# Main-board-4.net
KiCad netlist of a schematic drawn in EAGLE
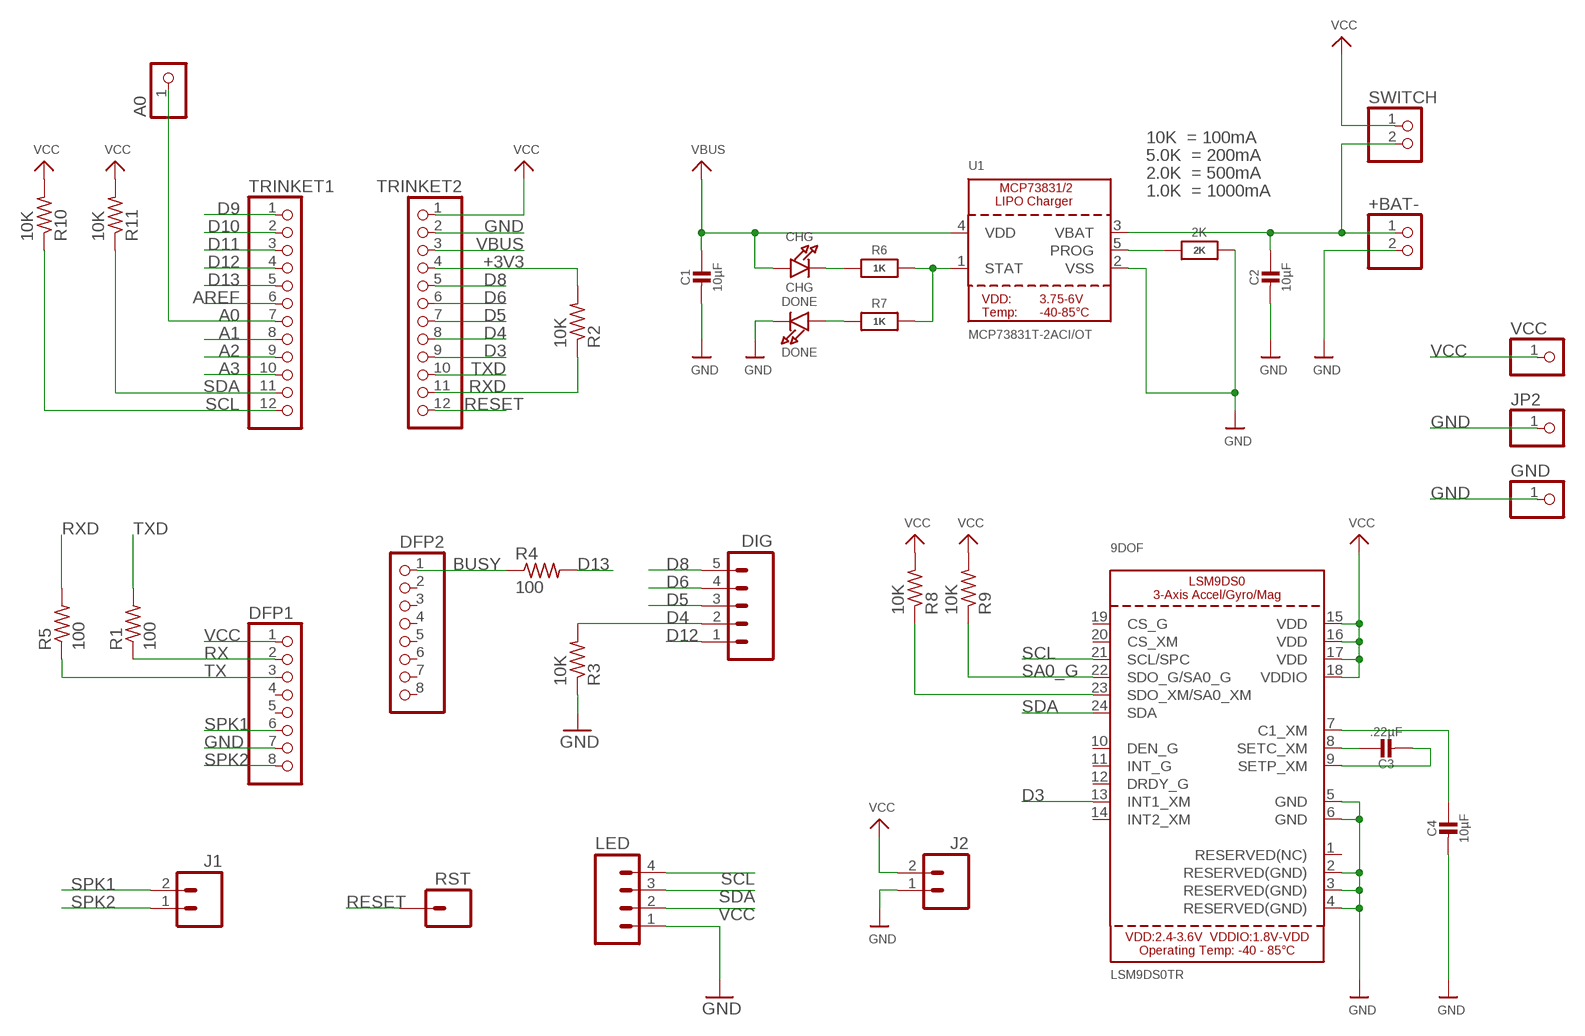
[diagram p0: schematic, sheet 1]

(export (version "E")
  (design (tool "Eeschema 10.0.6"))
  (components
    (comp (ref "+BAT-")
      (value "HEADER-1X2ROUND")
      (footprint "eagle-import:1X02_ROUND")
      (libsource (lib "eagle-import") (part "HEADER-1X2ROUND"))
    )
    (comp (ref "2K")
      (value "2K")
      (footprint "eagle-import:_0805MP")
      (libsource (lib "eagle-import") (part "RESISTOR_0805MP"))
    )
    (comp (ref "9DOF")
      (value "LSM9DS0TR")
      (footprint "eagle-import:LGA24_4X4MM")
      (libsource (lib "eagle-import") (part "LSM9DS0"))
    )
    (comp (ref "A0")
      (value "PINHD-1X1CB")
      (footprint "eagle-import:1X01-CLEANBIG")
      (libsource (lib "eagle-import") (part "PINHD-1X1CB"))
    )
    (comp (ref "C1")
      (value "10µF")
      (footprint "eagle-import:0805-NO")
      (libsource (lib "eagle-import") (part "CAP_CERAMIC0805-NOOUTLINE"))
    )
    (comp (ref "C2")
      (value "10µF")
      (footprint "eagle-import:0805-NO")
      (libsource (lib "eagle-import") (part "CAP_CERAMIC0805-NOOUTLINE"))
    )
    (comp (ref "C3")
      (value ".22µF")
      (footprint "eagle-import:0805-NO")
      (libsource (lib "eagle-import") (part "CAP_CERAMIC0805-NOOUTLINE"))
    )
    (comp (ref "C4")
      (value "10µF")
      (footprint "eagle-import:0805-NO")
      (libsource (lib "eagle-import") (part "CAP_CERAMIC0805-NOOUTLINE"))
    )
    (comp (ref "CHG")
      (value "CHG")
      (footprint "eagle-import:CHIPLED_0805_NOOUTLINE")
      (libsource (lib "eagle-import") (part "LED0805_NOOUTLINE"))
    )
    (comp (ref "DFP1")
      (value "PINHD-1X8CLEANBIG")
      (footprint "eagle-import:1X08-CLEANBIG")
      (libsource (lib "eagle-import") (part "PINHD-1X8CLEANBIG"))
    )
    (comp (ref "DFP2")
      (value "PINHD-1X8CLEANBIG")
      (footprint "eagle-import:1X08-CLEANBIG")
      (libsource (lib "eagle-import") (part "PINHD-1X8CLEANBIG"))
    )
    (comp (ref "DIG")
      (value "M05NO_SILK")
      (footprint "eagle-import:1X05_NO_SILK")
      (libsource (lib "eagle-import") (part "M05NO_SILK"))
    )
    (comp (ref "DONE")
      (value "DONE")
      (footprint "eagle-import:CHIPLED_0805_NOOUTLINE")
      (libsource (lib "eagle-import") (part "LED0805_NOOUTLINE"))
    )
    (comp (ref "GND")
      (value "PINHD-1X1CB")
      (footprint "eagle-import:1X01-CLEANBIG")
      (libsource (lib "eagle-import") (part "PINHD-1X1CB"))
    )
    (comp (ref "J1")
      (value "M021X02_NO_SILK")
      (footprint "eagle-import:1X02_NO_SILK")
      (libsource (lib "eagle-import") (part "M021X02_NO_SILK"))
    )
    (comp (ref "J2")
      (value "M021X02_NO_SILK")
      (footprint "eagle-import:1X02_NO_SILK")
      (libsource (lib "eagle-import") (part "M021X02_NO_SILK"))
    )
    (comp (ref "JP2")
      (value "PINHD-1X1CB")
      (footprint "eagle-import:1X01-CLEANBIG")
      (libsource (lib "eagle-import") (part "PINHD-1X1CB"))
    )
    (comp (ref "LED")
      (value "M04NO_SILK_ALL_ROUND")
      (footprint "eagle-import:1X04_NO_SILK_ALL_ROUND")
      (libsource (lib "eagle-import") (part "M04NO_SILK_ALL_ROUND"))
    )
    (comp (ref "R1")
      (value "100")
      (footprint "eagle-import:R0805")
      (libsource (lib "eagle-import") (part "R-US_R0805"))
    )
    (comp (ref "R2")
      (value "10K")
      (footprint "eagle-import:R0805")
      (libsource (lib "eagle-import") (part "R-US_R0805"))
    )
    (comp (ref "R3")
      (value "10K")
      (footprint "eagle-import:R0805")
      (libsource (lib "eagle-import") (part "R-US_R0805"))
    )
    (comp (ref "R4")
      (value "100")
      (footprint "eagle-import:R0805")
      (libsource (lib "eagle-import") (part "R-US_R0805"))
    )
    (comp (ref "R5")
      (value "100")
      (footprint "eagle-import:R0805")
      (libsource (lib "eagle-import") (part "R-US_R0805"))
    )
    (comp (ref "R6")
      (value "1K")
      (footprint "eagle-import:0805-NO")
      (libsource (lib "eagle-import") (part "RESISTOR0805_NOOUTLINE"))
    )
    (comp (ref "R7")
      (value "1K")
      (footprint "eagle-import:0805-NO")
      (libsource (lib "eagle-import") (part "RESISTOR0805_NOOUTLINE"))
    )
    (comp (ref "R8")
      (value "10K")
      (footprint "eagle-import:R0805")
      (libsource (lib "eagle-import") (part "R-US_R0805"))
    )
    (comp (ref "R9")
      (value "10K")
      (footprint "eagle-import:R0805")
      (libsource (lib "eagle-import") (part "R-US_R0805"))
    )
    (comp (ref "R10")
      (value "10K")
      (footprint "eagle-import:R0805")
      (libsource (lib "eagle-import") (part "R-US_R0805"))
    )
    (comp (ref "R11")
      (value "10K")
      (footprint "eagle-import:R0805")
      (libsource (lib "eagle-import") (part "R-US_R0805"))
    )
    (comp (ref "RST")
      (value "M01PTH_NO_SILK_YES_STOP")
      (footprint "eagle-import:1X01_NO_SILK")
      (libsource (lib "eagle-import") (part "M01PTH_NO_SILK_YES_STOP"))
    )
    (comp (ref "SWITCH")
      (value "HEADER-1X2ROUND")
      (footprint "eagle-import:1X02_ROUND")
      (libsource (lib "eagle-import") (part "HEADER-1X2ROUND"))
    )
    (comp (ref "TRINKET1")
      (value "PINHD-1X12-CB")
      (footprint "eagle-import:1X12-CB")
      (libsource (lib "eagle-import") (part "PINHD-1X12-CB"))
    )
    (comp (ref "TRINKET2")
      (value "PINHD-1X12-CB")
      (footprint "eagle-import:1X12-CB")
      (libsource (lib "eagle-import") (part "PINHD-1X12-CB"))
    )
    (comp (ref "U1")
      (value "MCP73831T-2ACI/OT")
      (footprint "eagle-import:SOT23-5")
      (libsource (lib "eagle-import") (part "MCP73831/2"))
    )
    (comp (ref "VCC")
      (value "PINHD-1X1CB")
      (footprint "eagle-import:1X01-CLEANBIG")
      (libsource (lib "eagle-import") (part "PINHD-1X1CB"))
    )
  )
  (nets
    (net (code "1") (name "/+3V3") (class "Default")
      (node (ref "R2") (pin "2") (pinfunction "2_2") (pintype "passive"))
      (node (ref "TRINKET2") (pin "4") (pinfunction "4_4") (pintype "passive"))
    )
    (net (code "2") (name "/A0") (class "Default")
      (node (ref "A0") (pin "1") (pinfunction "1_1") (pintype "passive"))
      (node (ref "TRINKET1") (pin "7") (pinfunction "7_7") (pintype "passive"))
    )
    (net (code "3") (name "/A1") (class "Default")
      (node (ref "TRINKET1") (pin "8") (pinfunction "8_8") (pintype "passive"))
    )
    (net (code "4") (name "/A2") (class "Default")
      (node (ref "TRINKET1") (pin "9") (pinfunction "9_9") (pintype "passive"))
    )
    (net (code "5") (name "/A3") (class "Default")
      (node (ref "TRINKET1") (pin "10") (pinfunction "10_10") (pintype "passive"))
    )
    (net (code "6") (name "/AREF") (class "Default")
      (node (ref "TRINKET1") (pin "6") (pinfunction "6_6") (pintype "passive"))
    )
    (net (code "7") (name "/BUSY") (class "Default")
      (node (ref "DFP2") (pin "1") (pinfunction "1_1") (pintype "passive"))
      (node (ref "R4") (pin "1") (pinfunction "1_1") (pintype "passive"))
    )
    (net (code "8") (name "/D3") (class "Default")
      (node (ref "9DOF") (pin "13") (pinfunction "INT1_XM_13") (pintype "bidirectional"))
      (node (ref "TRINKET2") (pin "9") (pinfunction "9_9") (pintype "passive"))
    )
    (net (code "9") (name "/D4") (class "Default")
      (node (ref "DIG") (pin "2") (pinfunction "2_2") (pintype "passive"))
      (node (ref "R3") (pin "2") (pinfunction "2_2") (pintype "passive"))
      (node (ref "TRINKET2") (pin "8") (pinfunction "8_8") (pintype "passive"))
    )
    (net (code "10") (name "/D5") (class "Default")
      (node (ref "DIG") (pin "3") (pinfunction "3_3") (pintype "passive"))
      (node (ref "TRINKET2") (pin "7") (pinfunction "7_7") (pintype "passive"))
    )
    (net (code "11") (name "/D6") (class "Default")
      (node (ref "DIG") (pin "4") (pinfunction "4_4") (pintype "passive"))
      (node (ref "TRINKET2") (pin "6") (pinfunction "6_6") (pintype "passive"))
    )
    (net (code "12") (name "/D8") (class "Default")
      (node (ref "DIG") (pin "5") (pinfunction "5_5") (pintype "passive"))
      (node (ref "TRINKET2") (pin "5") (pinfunction "5_5") (pintype "passive"))
    )
    (net (code "13") (name "/D9") (class "Default")
      (node (ref "TRINKET1") (pin "1") (pinfunction "1_1") (pintype "passive"))
    )
    (net (code "14") (name "/D10") (class "Default")
      (node (ref "TRINKET1") (pin "2") (pinfunction "2_2") (pintype "passive"))
    )
    (net (code "15") (name "/D11") (class "Default")
      (node (ref "TRINKET1") (pin "3") (pinfunction "3_3") (pintype "passive"))
    )
    (net (code "16") (name "/D12") (class "Default")
      (node (ref "DIG") (pin "1") (pinfunction "1_1") (pintype "passive"))
      (node (ref "TRINKET1") (pin "4") (pinfunction "4_4") (pintype "passive"))
    )
    (net (code "17") (name "/D13") (class "Default")
      (node (ref "R4") (pin "2") (pinfunction "2_2") (pintype "passive"))
      (node (ref "TRINKET1") (pin "5") (pinfunction "5_5") (pintype "passive"))
    )
    (net (code "18") (name "/RESET") (class "Default")
      (node (ref "RST") (pin "1") (pinfunction "1_1") (pintype "passive"))
      (node (ref "TRINKET2") (pin "12") (pinfunction "12_12") (pintype "passive"))
    )
    (net (code "19") (name "/RX") (class "Default")
      (node (ref "DFP1") (pin "2") (pinfunction "2_2") (pintype "passive"))
      (node (ref "R1") (pin "1") (pinfunction "1_1") (pintype "passive"))
    )
    (net (code "20") (name "/RXD") (class "Default")
      (node (ref "R2") (pin "1") (pinfunction "1_1") (pintype "passive"))
      (node (ref "R5") (pin "2") (pinfunction "2_2") (pintype "passive"))
      (node (ref "TRINKET2") (pin "11") (pinfunction "11_11") (pintype "passive"))
    )
    (net (code "21") (name "/SA0_G") (class "Default")
      (node (ref "9DOF") (pin "22") (pinfunction "SDO_G/SA0_G_22") (pintype "bidirectional"))
      (node (ref "R9") (pin "1") (pinfunction "1_1") (pintype "passive"))
    )
    (net (code "22") (name "/SCL") (class "Default")
      (node (ref "9DOF") (pin "21") (pinfunction "SCL/SPC_21") (pintype "bidirectional"))
      (node (ref "LED") (pin "4") (pinfunction "4_4") (pintype "passive"))
      (node (ref "R10") (pin "1") (pinfunction "1_1") (pintype "passive"))
      (node (ref "TRINKET1") (pin "12") (pinfunction "12_12") (pintype "passive"))
    )
    (net (code "23") (name "/SDA") (class "Default")
      (node (ref "9DOF") (pin "24") (pinfunction "SDA_24") (pintype "bidirectional"))
      (node (ref "LED") (pin "3") (pinfunction "3_3") (pintype "passive"))
      (node (ref "R11") (pin "1") (pinfunction "1_1") (pintype "passive"))
      (node (ref "TRINKET1") (pin "11") (pinfunction "11_11") (pintype "passive"))
    )
    (net (code "24") (name "/SPK1") (class "Default")
      (node (ref "DFP1") (pin "6") (pinfunction "6_6") (pintype "passive"))
      (node (ref "J1") (pin "2") (pinfunction "2_2") (pintype "passive"))
    )
    (net (code "25") (name "/SPK2") (class "Default")
      (node (ref "DFP1") (pin "8") (pinfunction "8_8") (pintype "passive"))
      (node (ref "J1") (pin "1") (pinfunction "1_1") (pintype "passive"))
    )
    (net (code "26") (name "/TX") (class "Default")
      (node (ref "DFP1") (pin "3") (pinfunction "3_3") (pintype "passive"))
      (node (ref "R5") (pin "1") (pinfunction "1_1") (pintype "passive"))
    )
    (net (code "27") (name "/TXD") (class "Default")
      (node (ref "R1") (pin "2") (pinfunction "2_2") (pintype "passive"))
      (node (ref "TRINKET2") (pin "10") (pinfunction "10_10") (pintype "passive"))
    )
    (net (code "28") (name "GND") (class "Default")
      (node (ref "+BAT-") (pin "2") (pinfunction "2_2") (pintype "passive"))
      (node (ref "2K") (pin "2") (pinfunction "2_2") (pintype "passive"))
      (node (ref "9DOF") (pin "2") (pinfunction "RESERVED(GND)_2") (pintype "power_in"))
      (node (ref "9DOF") (pin "3") (pinfunction "RESERVED(GND)_3") (pintype "power_in"))
      (node (ref "9DOF") (pin "4") (pinfunction "RESERVED(GND)_4") (pintype "power_in"))
      (node (ref "9DOF") (pin "5") (pinfunction "GND_5") (pintype "power_in"))
      (node (ref "9DOF") (pin "6") (pinfunction "GND_6") (pintype "power_in"))
      (node (ref "C1") (pin "2") (pinfunction "2_2") (pintype "passive"))
      (node (ref "C2") (pin "2") (pinfunction "2_2") (pintype "passive"))
      (node (ref "C4") (pin "2") (pinfunction "2_2") (pintype "passive"))
      (node (ref "DFP1") (pin "7") (pinfunction "7_7") (pintype "passive"))
      (node (ref "DONE") (pin "C") (pinfunction "C_C") (pintype "passive"))
      (node (ref "GND") (pin "1") (pinfunction "1_1") (pintype "passive"))
      (node (ref "J2") (pin "1") (pinfunction "1_1") (pintype "passive"))
      (node (ref "JP2") (pin "1") (pinfunction "1_1") (pintype "passive"))
      (node (ref "LED") (pin "1") (pinfunction "1_1") (pintype "passive"))
      (node (ref "R3") (pin "1") (pinfunction "1_1") (pintype "passive"))
      (node (ref "TRINKET2") (pin "2") (pinfunction "2_2") (pintype "passive"))
      (node (ref "U1") (pin "2") (pinfunction "VSS_2") (pintype "power_in"))
    )
    (net (code "29") (name "Net-(9DOF-C1_XM)") (class "Default")
      (node (ref "9DOF") (pin "7") (pinfunction "C1_XM_7") (pintype "bidirectional"))
      (node (ref "C4") (pin "1") (pinfunction "1_1") (pintype "passive"))
    )
    (net (code "30") (name "Net-(9DOF-SDO_XM{slash}SA0_XM)") (class "Default")
      (node (ref "9DOF") (pin "23") (pinfunction "SDO_XM/SA0_XM_23") (pintype "bidirectional"))
      (node (ref "R8") (pin "1") (pinfunction "1_1") (pintype "passive"))
    )
    (net (code "31") (name "Net-(9DOF-SETC_XM)") (class "Default")
      (node (ref "9DOF") (pin "8") (pinfunction "SETC_XM_8") (pintype "bidirectional"))
      (node (ref "C3") (pin "1") (pinfunction "1_1") (pintype "passive"))
    )
    (net (code "32") (name "Net-(9DOF-SETP_XM)") (class "Default")
      (node (ref "9DOF") (pin "9") (pinfunction "SETP_XM_9") (pintype "bidirectional"))
      (node (ref "C3") (pin "2") (pinfunction "2_2") (pintype "passive"))
    )
    (net (code "33") (name "Net-(CHG-PadC)") (class "Default")
      (node (ref "CHG") (pin "C") (pinfunction "C_C") (pintype "passive"))
      (node (ref "R6") (pin "1") (pinfunction "1_1") (pintype "passive"))
    )
    (net (code "34") (name "Net-(DONE-PadA)") (class "Default")
      (node (ref "DONE") (pin "A") (pinfunction "A_A") (pintype "passive"))
      (node (ref "R7") (pin "1") (pinfunction "1_1") (pintype "passive"))
    )
    (net (code "35") (name "Net-(U1-PROG)") (class "Default")
      (node (ref "2K") (pin "1") (pinfunction "1_1") (pintype "passive"))
      (node (ref "U1") (pin "5") (pinfunction "PROG_5") (pintype "input"))
    )
    (net (code "36") (name "Net-(U1-STAT)") (class "Default")
      (node (ref "R6") (pin "2") (pinfunction "2_2") (pintype "passive"))
      (node (ref "R7") (pin "2") (pinfunction "2_2") (pintype "passive"))
      (node (ref "U1") (pin "1") (pinfunction "STAT_1") (pintype "output"))
    )
    (net (code "37") (name "Net-(U1-VBAT)") (class "Default")
      (node (ref "+BAT-") (pin "1") (pinfunction "1_1") (pintype "passive"))
      (node (ref "C2") (pin "1") (pinfunction "1_1") (pintype "passive"))
      (node (ref "SWITCH") (pin "2") (pinfunction "2_2") (pintype "passive"))
      (node (ref "U1") (pin "3") (pinfunction "VBAT_3") (pintype "power_in"))
    )
    (net (code "38") (name "VBUS") (class "Default")
      (node (ref "C1") (pin "1") (pinfunction "1_1") (pintype "passive"))
      (node (ref "CHG") (pin "A") (pinfunction "A_A") (pintype "passive"))
      (node (ref "TRINKET2") (pin "3") (pinfunction "3_3") (pintype "passive"))
      (node (ref "U1") (pin "4") (pinfunction "VDD_4") (pintype "power_in"))
    )
    (net (code "39") (name "VCC") (class "Default")
      (node (ref "9DOF") (pin "15") (pinfunction "VDD_15") (pintype "power_in"))
      (node (ref "9DOF") (pin "16") (pinfunction "VDD_16") (pintype "power_in"))
      (node (ref "9DOF") (pin "17") (pinfunction "VDD_17") (pintype "power_in"))
      (node (ref "9DOF") (pin "18") (pinfunction "VDDIO_18") (pintype "power_in"))
      (node (ref "DFP1") (pin "1") (pinfunction "1_1") (pintype "passive"))
      (node (ref "J2") (pin "2") (pinfunction "2_2") (pintype "passive"))
      (node (ref "LED") (pin "2") (pinfunction "2_2") (pintype "passive"))
      (node (ref "R10") (pin "2") (pinfunction "2_2") (pintype "passive"))
      (node (ref "R11") (pin "2") (pinfunction "2_2") (pintype "passive"))
      (node (ref "R8") (pin "2") (pinfunction "2_2") (pintype "passive"))
      (node (ref "R9") (pin "2") (pinfunction "2_2") (pintype "passive"))
      (node (ref "SWITCH") (pin "1") (pinfunction "1_1") (pintype "passive"))
      (node (ref "TRINKET2") (pin "1") (pinfunction "1_1") (pintype "passive"))
      (node (ref "VCC") (pin "1") (pinfunction "1_1") (pintype "passive"))
    )
    (net (code "40") (name "unconnected-(9DOF-CS_G-Pad19)") (class "Default")
      (node (ref "9DOF") (pin "19") (pinfunction "CS_G_19") (pintype "bidirectional"))
    )
    (net (code "41") (name "unconnected-(9DOF-CS_XM-Pad20)") (class "Default")
      (node (ref "9DOF") (pin "20") (pinfunction "CS_XM_20") (pintype "bidirectional"))
    )
    (net (code "42") (name "unconnected-(9DOF-DEN_G-Pad10)") (class "Default")
      (node (ref "9DOF") (pin "10") (pinfunction "DEN_G_10") (pintype "bidirectional"))
    )
    (net (code "43") (name "unconnected-(9DOF-DRDY_G-Pad12)") (class "Default")
      (node (ref "9DOF") (pin "12") (pinfunction "DRDY_G_12") (pintype "bidirectional"))
    )
    (net (code "44") (name "unconnected-(9DOF-INT2_XM-Pad14)") (class "Default")
      (node (ref "9DOF") (pin "14") (pinfunction "INT2_XM_14") (pintype "bidirectional"))
    )
    (net (code "45") (name "unconnected-(9DOF-INT_G-Pad11)") (class "Default")
      (node (ref "9DOF") (pin "11") (pinfunction "INT_G_11") (pintype "bidirectional"))
    )
    (net (code "46") (name "unconnected-(9DOF-RESERVED(NC)-Pad1)") (class "Default")
      (node (ref "9DOF") (pin "1") (pinfunction "RESERVED(NC)_1") (pintype "no_connect"))
    )
    (net (code "47") (name "unconnected-(DFP1-Pad4)") (class "Default")
      (node (ref "DFP1") (pin "4") (pinfunction "4_4") (pintype "passive"))
    )
    (net (code "48") (name "unconnected-(DFP1-Pad5)") (class "Default")
      (node (ref "DFP1") (pin "5") (pinfunction "5_5") (pintype "passive"))
    )
    (net (code "49") (name "unconnected-(DFP2-Pad2)") (class "Default")
      (node (ref "DFP2") (pin "2") (pinfunction "2_2") (pintype "passive"))
    )
    (net (code "50") (name "unconnected-(DFP2-Pad3)") (class "Default")
      (node (ref "DFP2") (pin "3") (pinfunction "3_3") (pintype "passive"))
    )
    (net (code "51") (name "unconnected-(DFP2-Pad4)") (class "Default")
      (node (ref "DFP2") (pin "4") (pinfunction "4_4") (pintype "passive"))
    )
    (net (code "52") (name "unconnected-(DFP2-Pad5)") (class "Default")
      (node (ref "DFP2") (pin "5") (pinfunction "5_5") (pintype "passive"))
    )
    (net (code "53") (name "unconnected-(DFP2-Pad6)") (class "Default")
      (node (ref "DFP2") (pin "6") (pinfunction "6_6") (pintype "passive"))
    )
    (net (code "54") (name "unconnected-(DFP2-Pad7)") (class "Default")
      (node (ref "DFP2") (pin "7") (pinfunction "7_7") (pintype "passive"))
    )
    (net (code "55") (name "unconnected-(DFP2-Pad8)") (class "Default")
      (node (ref "DFP2") (pin "8") (pinfunction "8_8") (pintype "passive"))
    )
  )
)
